# sigfox_pcb.net
KiCad netlist of a schematic drawn in EAGLE
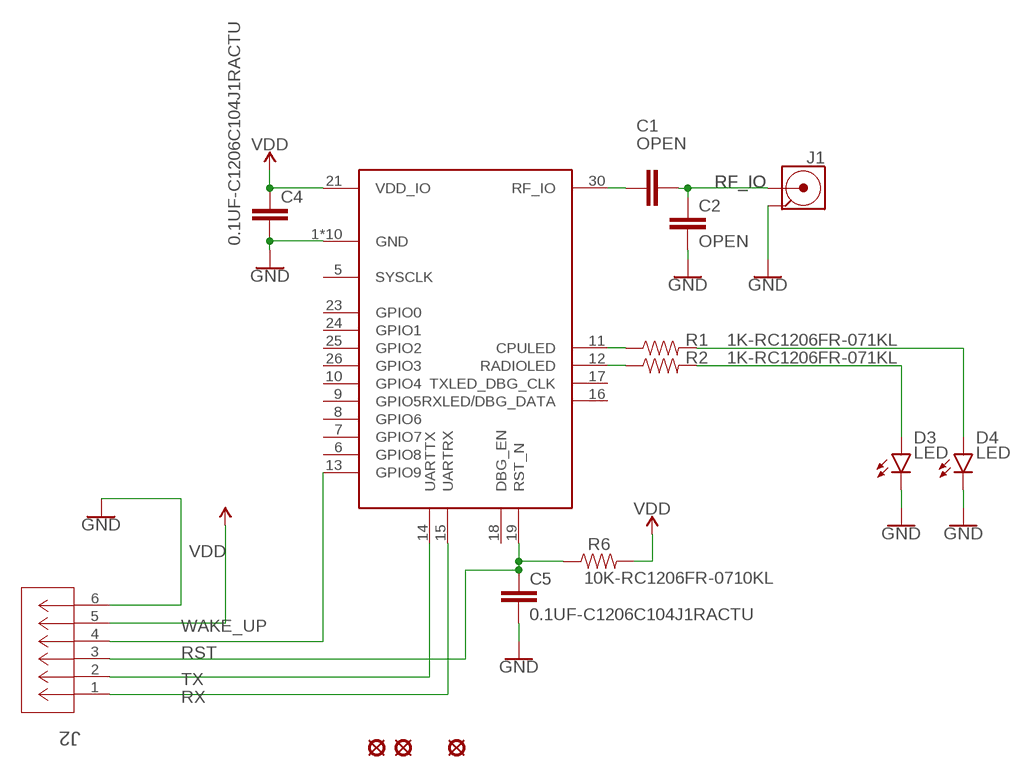
[diagram p0: schematic, sheet 1]

(export (version "E")
  (design (tool "Eeschema 10.0.6"))
  (components
    (comp (ref "C1")
      (value "OPEN")
      (footprint "eagle-import:C1206_OPEN")
      (libsource (lib "eagle-import") (part "OPEN"))
    )
    (comp (ref "C2")
      (value "OPEN")
      (footprint "eagle-import:C1206_OPEN")
      (libsource (lib "eagle-import") (part "OPEN"))
    )
    (comp (ref "C4")
      (value "0.1UF-C1206C104J1RACTU")
      (footprint "eagle-import:C1206")
      (fields (field (name "MFR") "KEMET"))
      (libsource (lib "eagle-import") (part "0.1UF-C1206C104J1RACTU"))
    )
    (comp (ref "C5")
      (value "0.1UF-C1206C104J1RACTU")
      (footprint "eagle-import:C1206")
      (fields (field (name "MFR") "KEMET"))
      (libsource (lib "eagle-import") (part "0.1UF-C1206C104J1RACTU"))
    )
    (comp (ref "D3")
      (value "LED")
      (footprint "eagle-import:LED1206")
      (libsource (lib "eagle-import") (part "LED"))
    )
    (comp (ref "D4")
      (value "LED")
      (footprint "eagle-import:LED1206")
      (libsource (lib "eagle-import") (part "LED"))
    )
    (comp (ref "H1")
      (value "HOLE-M3")
      (footprint "eagle-import:HOLE_3.0")
      (libsource (lib "eagle-import") (part "HOLE-M3"))
    )
    (comp (ref "H2")
      (value "HOLE-M3")
      (footprint "eagle-import:HOLE_3.0")
      (libsource (lib "eagle-import") (part "HOLE-M3"))
    )
    (comp (ref "H4")
      (value "HOLE-M3")
      (footprint "eagle-import:HOLE_3.0")
      (libsource (lib "eagle-import") (part "HOLE-M3"))
    )
    (comp (ref "J1")
      (value "SMA-142-0701-801")
      (footprint "eagle-import:142-0701-801")
      (fields (field (name "MFR") "Cinch Connectivity Solutions Johnson"))
      (libsource (lib "eagle-import") (part "SMA-142-0701-801"))
    )
    (comp (ref "J2")
      (value "SSW-106-02-G-S-RA")
      (footprint "eagle-import:CON6_1X6_TR_SSQ")
      (libsource (lib "eagle-import") (part "SSW-106-02-G-S-RA"))
    )
    (comp (ref "R1")
      (value "1K-RC1206FR-071KL")
      (footprint "eagle-import:R1206")
      (fields (field (name "MFR") "Yageo"))
      (libsource (lib "eagle-import") (part "1K-RC1206FR-071KL"))
    )
    (comp (ref "R2")
      (value "1K-RC1206FR-071KL")
      (footprint "eagle-import:R1206")
      (fields (field (name "MFR") "Yageo"))
      (libsource (lib "eagle-import") (part "1K-RC1206FR-071KL"))
    )
    (comp (ref "R6")
      (value "10K-RC1206FR-0710KL")
      (footprint "eagle-import:R1206")
      (fields (field (name "MFR") "Yageo"))
      (libsource (lib "eagle-import") (part "10K-RC1206FR-0710KL"))
    )
    (comp (ref "U1")
      (value "SFM11R2D")
      (footprint "eagle-import:SFM11R2D")
      (libsource (lib "eagle-import") (part "SFM11R2D"))
    )
  )
  (nets
    (net (code "1") (name "/RF_IO") (class "Default")
      (node (ref "C1") (pin "2") (pinfunction "2_2") (pintype "passive"))
      (node (ref "C2") (pin "1") (pinfunction "1_1") (pintype "passive"))
      (node (ref "J1") (pin "1") (pinfunction "1_1") (pintype "passive"))
    )
    (net (code "2") (name "/RST") (class "Default")
      (node (ref "C5") (pin "1") (pinfunction "1_1") (pintype "passive"))
      (node (ref "J2") (pin "3") (pinfunction "3_3") (pintype "passive"))
      (node (ref "R6") (pin "1") (pinfunction "1_1") (pintype "passive"))
      (node (ref "U1") (pin "19") (pinfunction "RST_N_19") (pintype "bidirectional"))
    )
    (net (code "3") (name "/RX") (class "Default")
      (node (ref "J2") (pin "1") (pinfunction "1_1") (pintype "passive"))
      (node (ref "U1") (pin "15") (pinfunction "UARTRX_15") (pintype "bidirectional"))
    )
    (net (code "4") (name "/TX") (class "Default")
      (node (ref "J2") (pin "2") (pinfunction "2_2") (pintype "passive"))
      (node (ref "U1") (pin "14") (pinfunction "UARTTX_14") (pintype "bidirectional"))
    )
    (net (code "5") (name "/WAKE_UP") (class "Default")
      (node (ref "J2") (pin "4") (pinfunction "4_4") (pintype "passive"))
      (node (ref "U1") (pin "13") (pinfunction "GPIO9_13") (pintype "bidirectional"))
    )
    (net (code "6") (name "GND") (class "Default")
      (node (ref "C2") (pin "2") (pinfunction "2_2") (pintype "passive"))
      (node (ref "C4") (pin "2") (pinfunction "2_2") (pintype "passive"))
      (node (ref "C5") (pin "2") (pinfunction "2_2") (pintype "passive"))
      (node (ref "D3") (pin "K") (pinfunction "C_K") (pintype "passive"))
      (node (ref "D4") (pin "K") (pinfunction "C_K") (pintype "passive"))
      (node (ref "J1") (pin "2_1") (pinfunction "2_2_1") (pintype "passive"))
      (node (ref "J1") (pin "2_2") (pinfunction "2_2_2") (pintype "passive"))
      (node (ref "J1") (pin "3_1") (pinfunction "2_3_1") (pintype "passive"))
      (node (ref "J1") (pin "3_2") (pinfunction "2_3_2") (pintype "passive"))
      (node (ref "J2") (pin "6") (pinfunction "6_6") (pintype "passive"))
      (node (ref "U1") (pin "1") (pinfunction "GND_1") (pintype "bidirectional"))
      (node (ref "U1") (pin "2") (pinfunction "GND_2") (pintype "bidirectional"))
      (node (ref "U1") (pin "20") (pinfunction "GND_20") (pintype "bidirectional"))
      (node (ref "U1") (pin "22") (pinfunction "GND_22") (pintype "bidirectional"))
      (node (ref "U1") (pin "27") (pinfunction "GND_27") (pintype "bidirectional"))
      (node (ref "U1") (pin "28") (pinfunction "GND_28") (pintype "bidirectional"))
      (node (ref "U1") (pin "29") (pinfunction "GND_29") (pintype "bidirectional"))
      (node (ref "U1") (pin "3") (pinfunction "GND_3") (pintype "bidirectional"))
      (node (ref "U1") (pin "31") (pinfunction "GND_31") (pintype "bidirectional"))
      (node (ref "U1") (pin "4") (pinfunction "GND_4") (pintype "bidirectional"))
    )
    (net (code "7") (name "Net-(D3-PadA)") (class "Default")
      (node (ref "D3") (pin "A") (pinfunction "A_A") (pintype "passive"))
      (node (ref "R2") (pin "2") (pinfunction "2_2") (pintype "passive"))
    )
    (net (code "8") (name "Net-(D4-PadA)") (class "Default")
      (node (ref "D4") (pin "A") (pinfunction "A_A") (pintype "passive"))
      (node (ref "R1") (pin "2") (pinfunction "2_2") (pintype "passive"))
    )
    (net (code "9") (name "Net-(U1-CPULED)") (class "Default")
      (node (ref "R1") (pin "1") (pinfunction "1_1") (pintype "passive"))
      (node (ref "U1") (pin "11") (pinfunction "CPULED_11") (pintype "bidirectional"))
    )
    (net (code "10") (name "Net-(U1-RADIOLED)") (class "Default")
      (node (ref "R2") (pin "1") (pinfunction "1_1") (pintype "passive"))
      (node (ref "U1") (pin "12") (pinfunction "RADIOLED_12") (pintype "bidirectional"))
    )
    (net (code "11") (name "Net-(U1-RF_IO)") (class "Default")
      (node (ref "C1") (pin "1") (pinfunction "1_1") (pintype "passive"))
      (node (ref "U1") (pin "30") (pinfunction "RF_IO_30") (pintype "bidirectional"))
    )
    (net (code "12") (name "VDD") (class "Default")
      (node (ref "C4") (pin "1") (pinfunction "1_1") (pintype "passive"))
      (node (ref "J2") (pin "5") (pinfunction "5_5") (pintype "passive"))
      (node (ref "R6") (pin "2") (pinfunction "2_2") (pintype "passive"))
      (node (ref "U1") (pin "21") (pinfunction "VDD_IO_21") (pintype "bidirectional"))
    )
    (net (code "13") (name "unconnected-(U1-DBG_EN-Pad18)") (class "Default")
      (node (ref "U1") (pin "18") (pinfunction "DBG_EN_18") (pintype "bidirectional"))
    )
    (net (code "14") (name "unconnected-(U1-GPIO0-Pad23)") (class "Default")
      (node (ref "U1") (pin "23") (pinfunction "GPIO0_23") (pintype "bidirectional"))
    )
    (net (code "15") (name "unconnected-(U1-GPIO1-Pad24)") (class "Default")
      (node (ref "U1") (pin "24") (pinfunction "GPIO1_24") (pintype "bidirectional"))
    )
    (net (code "16") (name "unconnected-(U1-GPIO2-Pad25)") (class "Default")
      (node (ref "U1") (pin "25") (pinfunction "GPIO2_25") (pintype "bidirectional"))
    )
    (net (code "17") (name "unconnected-(U1-GPIO3-Pad26)") (class "Default")
      (node (ref "U1") (pin "26") (pinfunction "GPIO3_26") (pintype "bidirectional"))
    )
    (net (code "18") (name "unconnected-(U1-GPIO4-Pad10)") (class "Default")
      (node (ref "U1") (pin "10") (pinfunction "GPIO4_10") (pintype "bidirectional"))
    )
    (net (code "19") (name "unconnected-(U1-GPIO5-Pad9)") (class "Default")
      (node (ref "U1") (pin "9") (pinfunction "GPIO5_9") (pintype "bidirectional"))
    )
    (net (code "20") (name "unconnected-(U1-GPIO6-Pad8)") (class "Default")
      (node (ref "U1") (pin "8") (pinfunction "GPIO6_8") (pintype "bidirectional"))
    )
    (net (code "21") (name "unconnected-(U1-GPIO7-Pad7)") (class "Default")
      (node (ref "U1") (pin "7") (pinfunction "GPIO7_7") (pintype "bidirectional"))
    )
    (net (code "22") (name "unconnected-(U1-GPIO8-Pad6)") (class "Default")
      (node (ref "U1") (pin "6") (pinfunction "GPIO8_6") (pintype "bidirectional"))
    )
    (net (code "23") (name "unconnected-(U1-RXLED{slash}DBG_DATA-Pad16)") (class "Default")
      (node (ref "U1") (pin "16") (pinfunction "RXLED/DBG_DATA_16") (pintype "bidirectional"))
    )
    (net (code "24") (name "unconnected-(U1-SYSCLK-Pad5)") (class "Default")
      (node (ref "U1") (pin "5") (pinfunction "SYSCLK_5") (pintype "bidirectional"))
    )
    (net (code "25") (name "unconnected-(U1-TXLED_DBG_CLK-Pad17)") (class "Default")
      (node (ref "U1") (pin "17") (pinfunction "TXLED_DBG_CLK_17") (pintype "bidirectional"))
    )
  )
)
